# Down.net
KiCad netlist of a schematic drawn in EAGLE
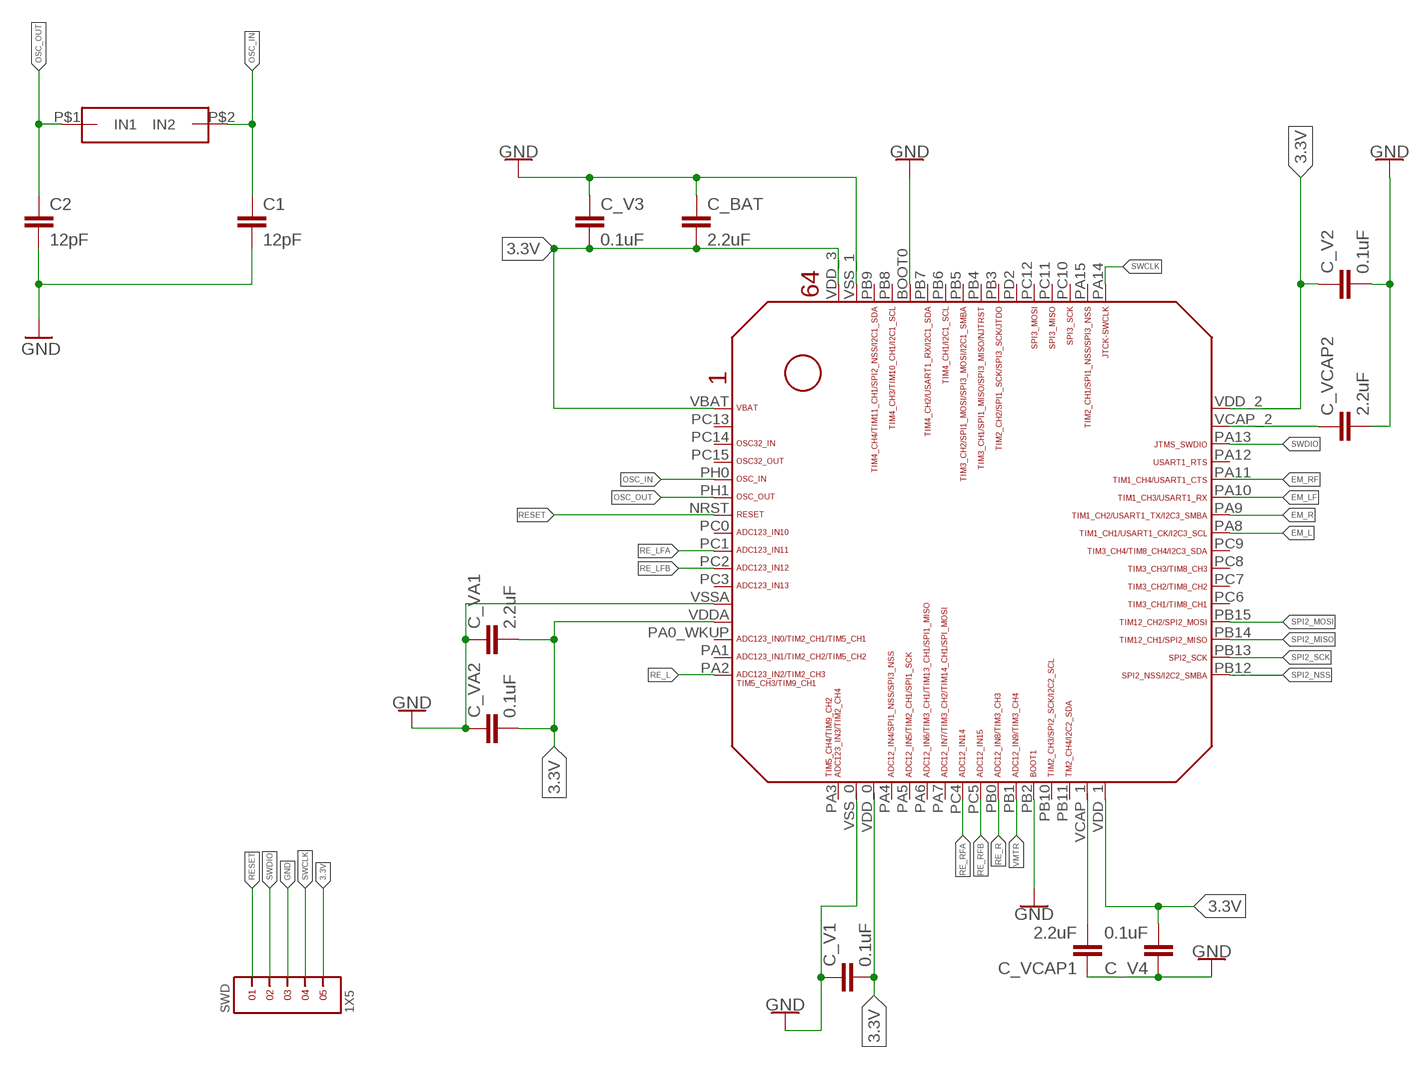
[diagram p0: schematic, sheet 1, part 1 of 3]
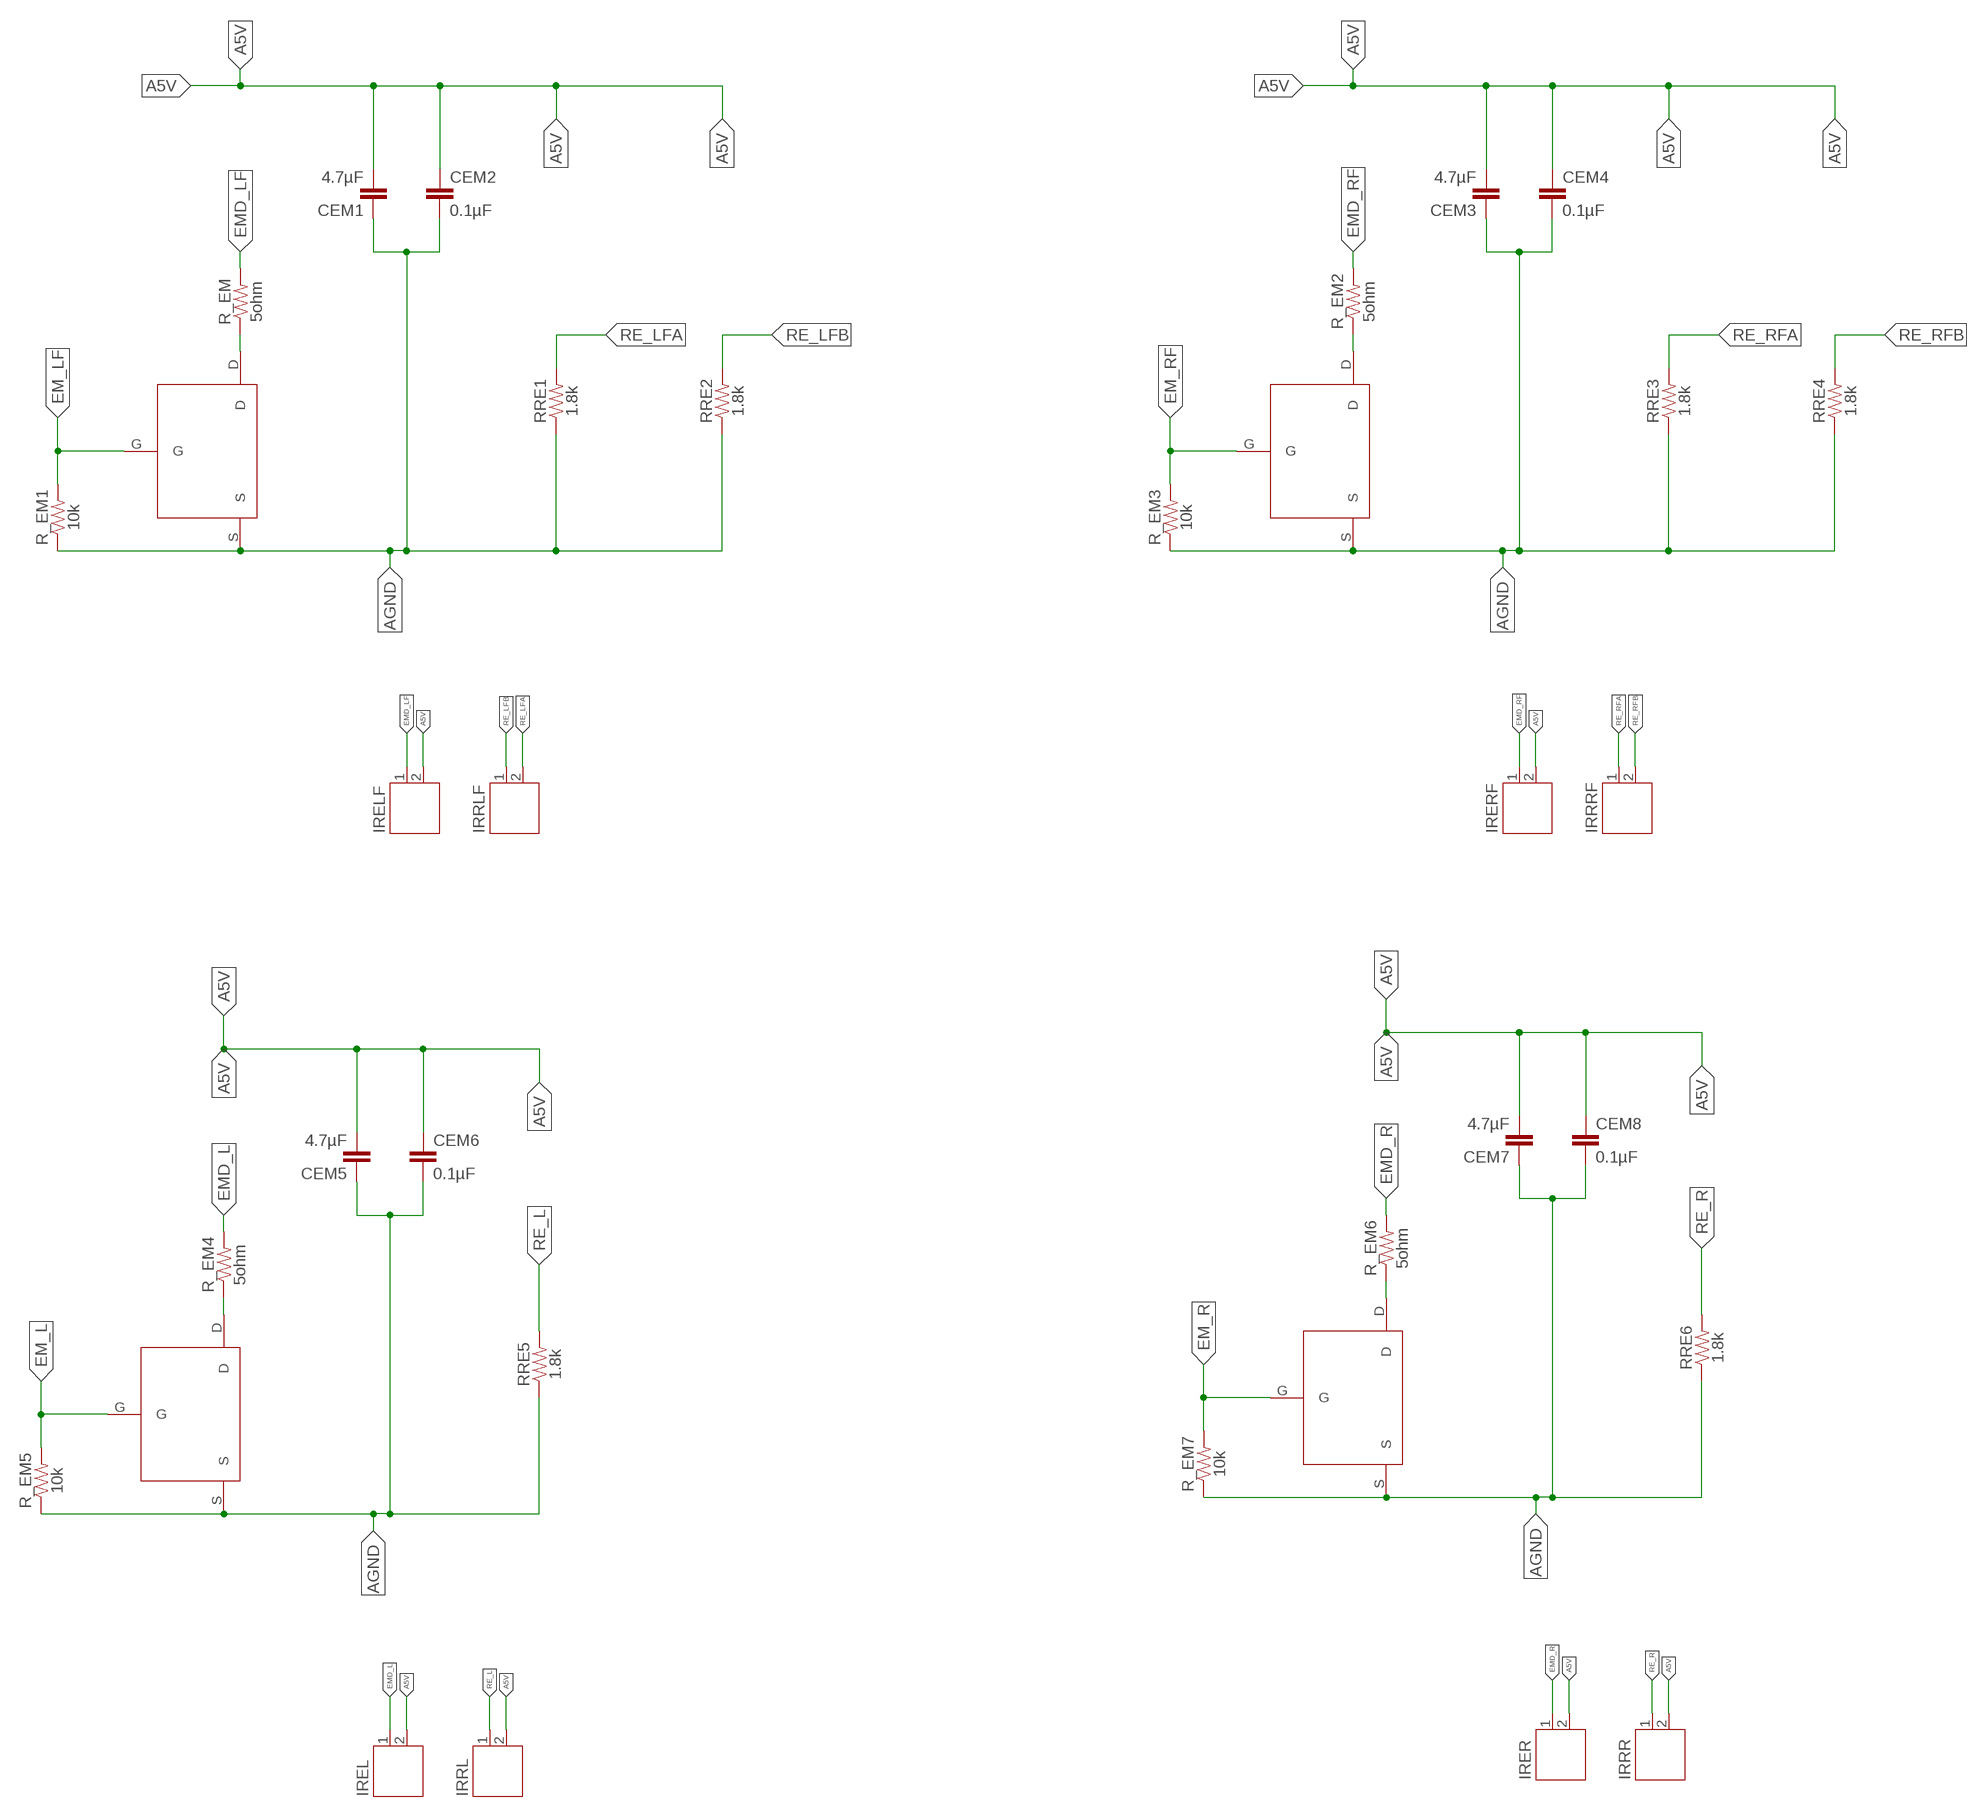
[diagram p1: schematic, sheet 1, part 2 of 3]
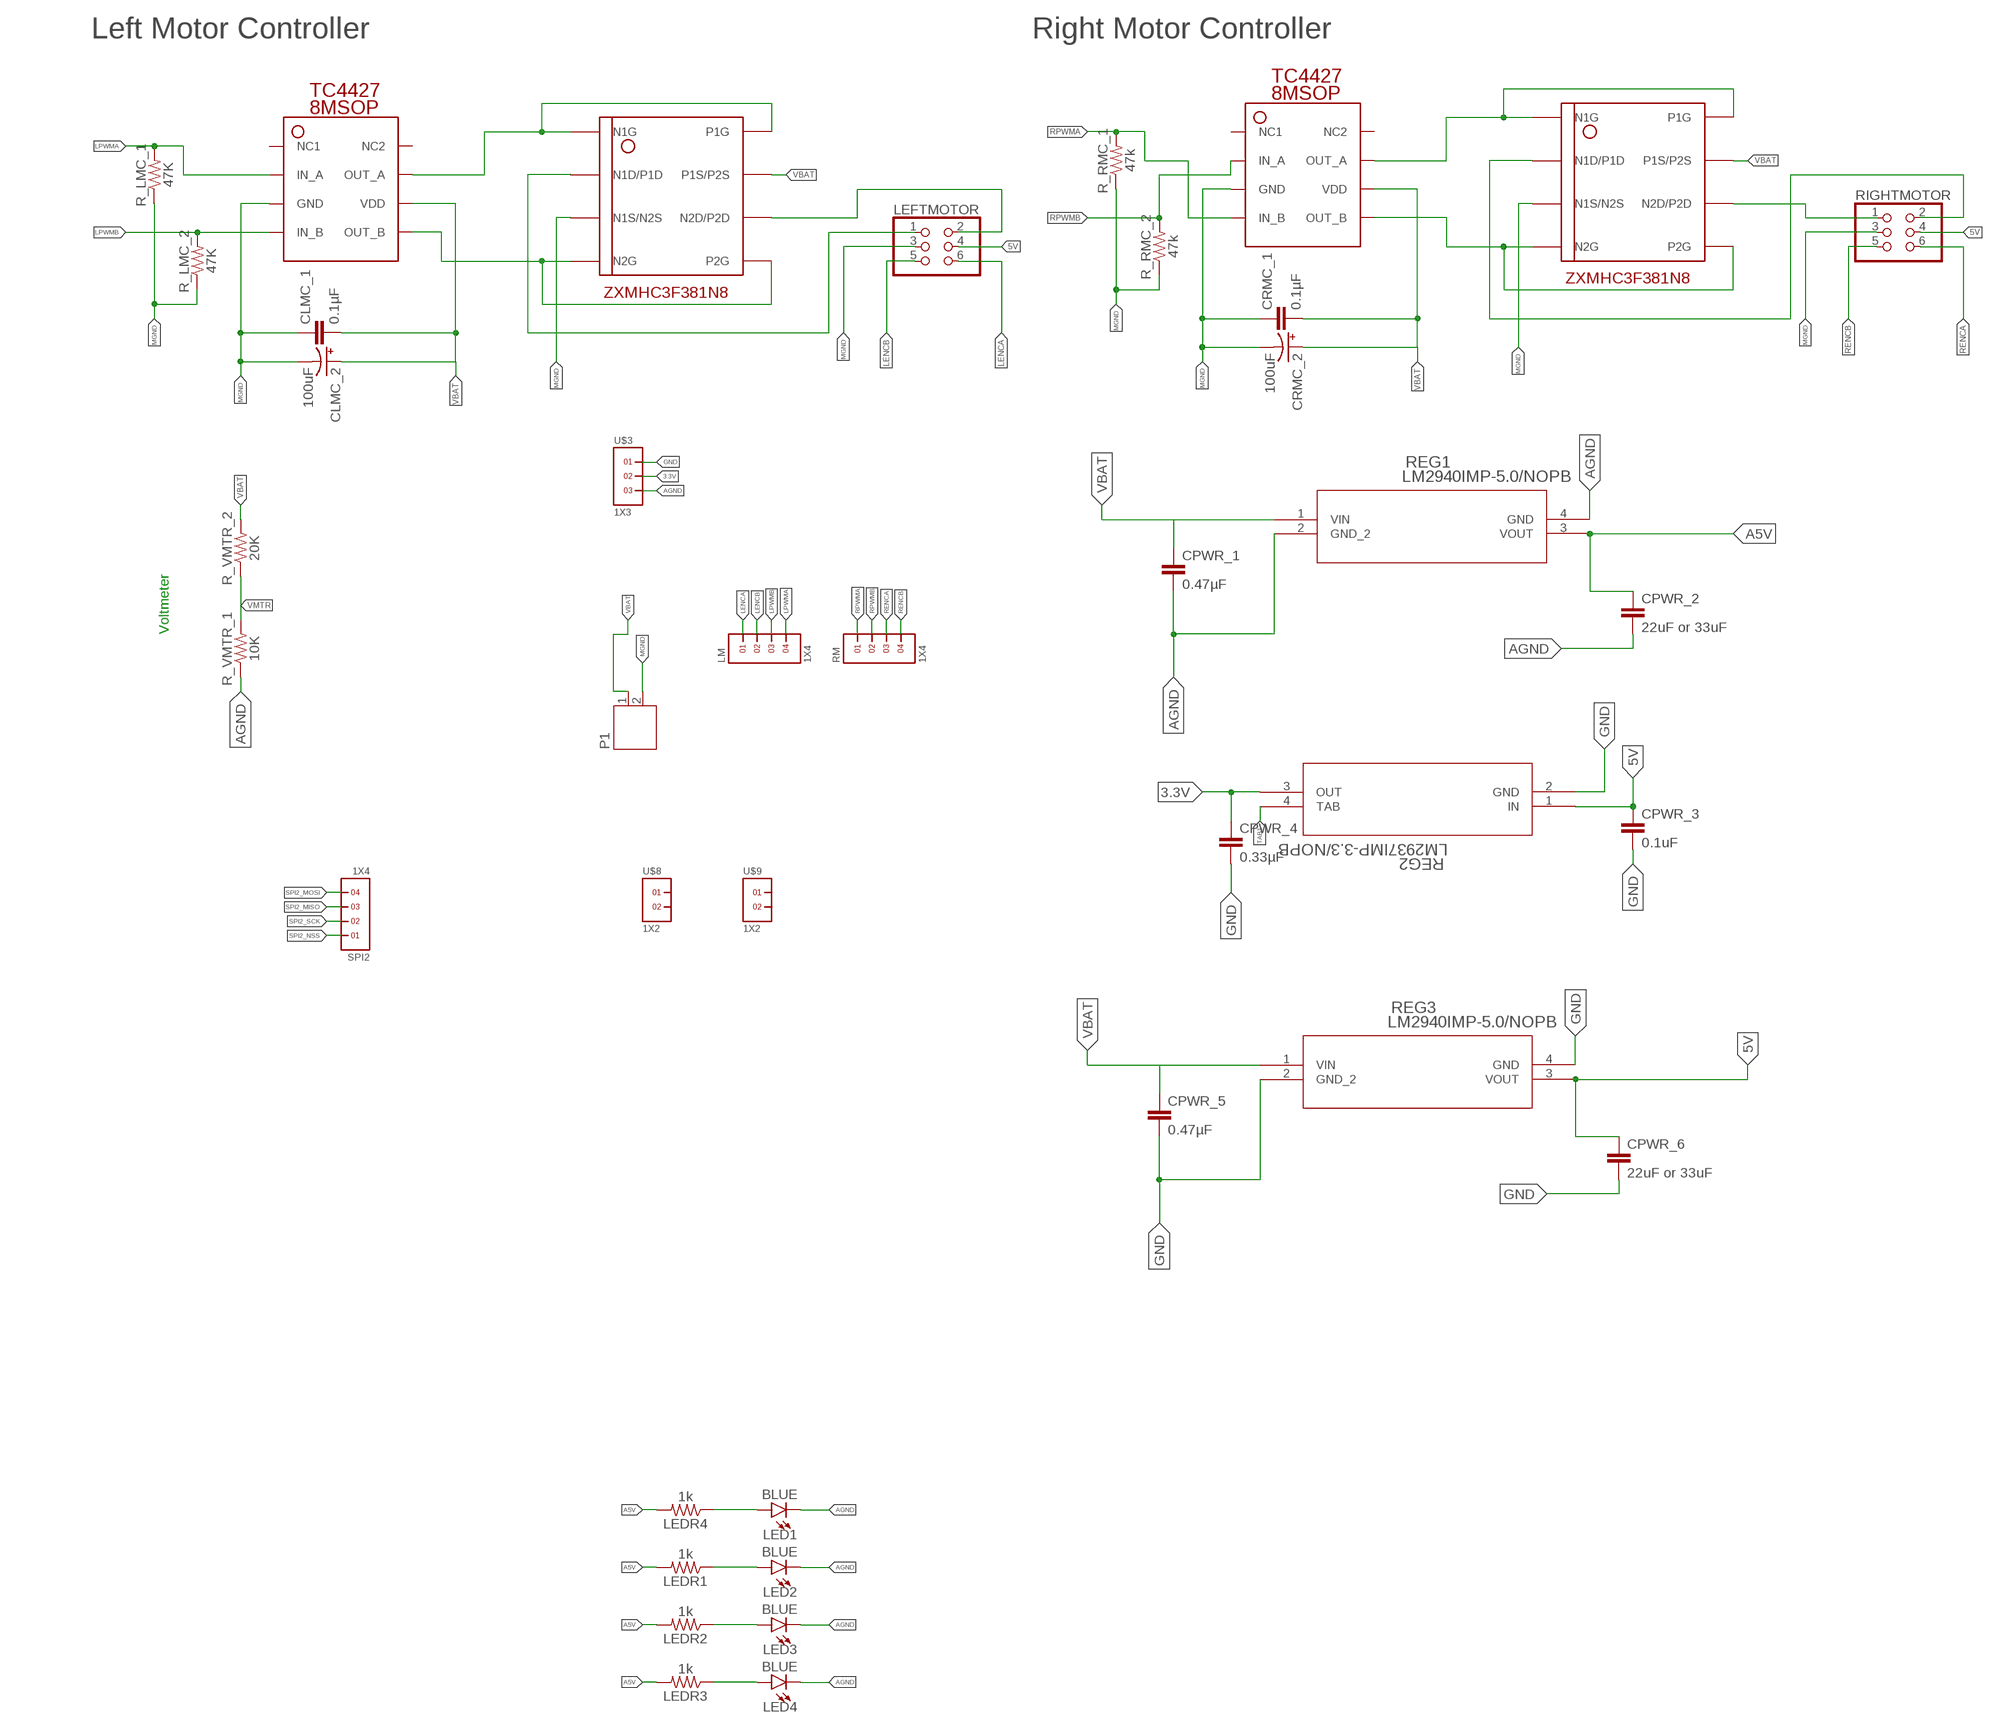
[diagram p2: schematic, sheet 1, part 3 of 3]

(export (version "E")
  (design (tool "Eeschema 10.0.6"))
  (components
    (comp (ref "C1")
      (value "12pF")
      (footprint "eagle-import:0603")
      (libsource (lib "eagle-import") (part "22PF-0603-50V-5%"))
    )
    (comp (ref "C2")
      (value "12pF")
      (footprint "eagle-import:0603")
      (libsource (lib "eagle-import") (part "22PF-0603-50V-5%"))
    )
    (comp (ref "CEM1")
      (value "4.7µF")
      (footprint "eagle-import:0805")
      (libsource (lib "eagle-import") (part "0.33UF/330NF-0805-50V-10%"))
    )
    (comp (ref "CEM2")
      (value "0.1µF")
      (footprint "eagle-import:0805")
      (libsource (lib "eagle-import") (part "0.33UF/330NF-0805-50V-10%"))
    )
    (comp (ref "CEM3")
      (value "4.7µF")
      (footprint "eagle-import:0805")
      (libsource (lib "eagle-import") (part "0.33UF/330NF-0805-50V-10%"))
    )
    (comp (ref "CEM4")
      (value "0.1µF")
      (footprint "eagle-import:0805")
      (libsource (lib "eagle-import") (part "0.33UF/330NF-0805-50V-10%"))
    )
    (comp (ref "CEM5")
      (value "4.7µF")
      (footprint "eagle-import:0805")
      (libsource (lib "eagle-import") (part "0.33UF/330NF-0805-50V-10%"))
    )
    (comp (ref "CEM6")
      (value "0.1µF")
      (footprint "eagle-import:0805")
      (libsource (lib "eagle-import") (part "0.33UF/330NF-0805-50V-10%"))
    )
    (comp (ref "CEM7")
      (value "4.7µF")
      (footprint "eagle-import:0805")
      (libsource (lib "eagle-import") (part "0.33UF/330NF-0805-50V-10%"))
    )
    (comp (ref "CEM8")
      (value "0.1µF")
      (footprint "eagle-import:0805")
      (libsource (lib "eagle-import") (part "0.33UF/330NF-0805-50V-10%"))
    )
    (comp (ref "CLMC_1")
      (value "0.1µF")
      (footprint "eagle-import:0805")
      (libsource (lib "eagle-import") (part "SparkFun-Capacitors_510_0.33UF/330NF-0805-50V-10%"))
    )
    (comp (ref "CLMC_2")
      (value "100uF")
      (footprint "eagle-import:EIA7343")
      (libsource (lib "eagle-import") (part "100UF-POLAR-EIA7343-10V-10%(TANT)"))
    )
    (comp (ref "CPWR_1")
      (value "0.47µF")
      (footprint "eagle-import:0805")
      (libsource (lib "eagle-import") (part "0.33UF/330NF-0805-50V-10%"))
    )
    (comp (ref "CPWR_2")
      (value "22uF or 33uF")
      (footprint "eagle-import:0805")
      (libsource (lib "eagle-import") (part "0.33UF/330NF-0805-50V-10%"))
    )
    (comp (ref "CPWR_3")
      (value "0.1uF")
      (footprint "eagle-import:0805")
      (libsource (lib "eagle-import") (part "0.33UF/330NF-0805-50V-10%"))
    )
    (comp (ref "CPWR_4")
      (value "0.33µF")
      (footprint "eagle-import:0805")
      (libsource (lib "eagle-import") (part "0.33UF/330NF-0805-50V-10%"))
    )
    (comp (ref "CPWR_5")
      (value "0.47µF")
      (footprint "eagle-import:0805")
      (libsource (lib "eagle-import") (part "0.33UF/330NF-0805-50V-10%"))
    )
    (comp (ref "CPWR_6")
      (value "22uF or 33uF")
      (footprint "eagle-import:0805")
      (libsource (lib "eagle-import") (part "0.33UF/330NF-0805-50V-10%"))
    )
    (comp (ref "CRMC_1")
      (value "0.1µF")
      (footprint "eagle-import:0805")
      (libsource (lib "eagle-import") (part "SparkFun-Capacitors_510_0.33UF/330NF-0805-50V-10%"))
    )
    (comp (ref "CRMC_2")
      (value "100uF")
      (footprint "eagle-import:EIA7343")
      (libsource (lib "eagle-import") (part "100UF-POLAR-EIA7343-10V-10%(TANT)"))
    )
    (comp (ref "C_BAT")
      (value "2.2uF")
      (footprint "eagle-import:0805")
      (libsource (lib "eagle-import") (part "22UF-0805-6.3V-20%"))
    )
    (comp (ref "C_V1")
      (value "0.1uF")
      (footprint "eagle-import:0805")
      (libsource (lib "eagle-import") (part "22UF-0805-6.3V-20%"))
    )
    (comp (ref "C_V2")
      (value "0.1uF")
      (footprint "eagle-import:0805")
      (libsource (lib "eagle-import") (part "22UF-0805-6.3V-20%"))
    )
    (comp (ref "C_V3")
      (value "0.1uF")
      (footprint "eagle-import:0805")
      (libsource (lib "eagle-import") (part "22UF-0805-6.3V-20%"))
    )
    (comp (ref "C_V4")
      (value "0.1uF")
      (footprint "eagle-import:0805")
      (libsource (lib "eagle-import") (part "22UF-0805-6.3V-20%"))
    )
    (comp (ref "C_VA1")
      (value "2.2uF")
      (footprint "eagle-import:0805")
      (libsource (lib "eagle-import") (part "22UF-0805-6.3V-20%"))
    )
    (comp (ref "C_VA2")
      (value "0.1uF")
      (footprint "eagle-import:0805")
      (libsource (lib "eagle-import") (part "22UF-0805-6.3V-20%"))
    )
    (comp (ref "C_VCAP1")
      (value "2.2uF")
      (footprint "eagle-import:0805")
      (libsource (lib "eagle-import") (part "22UF-0805-6.3V-20%"))
    )
    (comp (ref "C_VCAP2")
      (value "2.2uF")
      (footprint "eagle-import:0805")
      (libsource (lib "eagle-import") (part "22UF-0805-6.3V-20%"))
    )
    (comp (ref "IREL")
      (value "JST-PH2")
      (footprint "eagle-import:JST-PH2")
      (libsource (lib "eagle-import") (part "JST-PH2"))
    )
    (comp (ref "IRELF")
      (value "JST-PH2")
      (footprint "eagle-import:JST-PH2")
      (libsource (lib "eagle-import") (part "JST-PH2"))
    )
    (comp (ref "IRER")
      (value "JST-PH2")
      (footprint "eagle-import:JST-PH2")
      (libsource (lib "eagle-import") (part "JST-PH2"))
    )
    (comp (ref "IRERF")
      (value "JST-PH2")
      (footprint "eagle-import:JST-PH2")
      (libsource (lib "eagle-import") (part "JST-PH2"))
    )
    (comp (ref "IRRL")
      (value "JST-PH2")
      (footprint "eagle-import:JST-PH2")
      (libsource (lib "eagle-import") (part "JST-PH2"))
    )
    (comp (ref "IRRLF")
      (value "JST-PH2")
      (footprint "eagle-import:JST-PH2")
      (libsource (lib "eagle-import") (part "JST-PH2"))
    )
    (comp (ref "IRRR")
      (value "JST-PH2")
      (footprint "eagle-import:JST-PH2")
      (libsource (lib "eagle-import") (part "JST-PH2"))
    )
    (comp (ref "IRRRF")
      (value "JST-PH2")
      (footprint "eagle-import:JST-PH2")
      (libsource (lib "eagle-import") (part "JST-PH2"))
    )
    (comp (ref "LED1")
      (value "BLUE")
      (footprint "eagle-import:LED-1206")
      (libsource (lib "eagle-import") (part "LED-BLUE1206"))
    )
    (comp (ref "LED2")
      (value "BLUE")
      (footprint "eagle-import:LED-1206")
      (libsource (lib "eagle-import") (part "LED-BLUE1206"))
    )
    (comp (ref "LED3")
      (value "BLUE")
      (footprint "eagle-import:LED-1206")
      (libsource (lib "eagle-import") (part "LED-BLUE1206"))
    )
    (comp (ref "LED4")
      (value "BLUE")
      (footprint "eagle-import:LED-1206")
      (libsource (lib "eagle-import") (part "LED-BLUE1206"))
    )
    (comp (ref "LEDR1")
      (value "1k")
      (footprint "eagle-import:0805")
      (libsource (lib "eagle-import") (part "0.75OHM-0805-1/4W-1%"))
    )
    (comp (ref "LEDR2")
      (value "1k")
      (footprint "eagle-import:0805")
      (libsource (lib "eagle-import") (part "0.75OHM-0805-1/4W-1%"))
    )
    (comp (ref "LEDR3")
      (value "1k")
      (footprint "eagle-import:0805")
      (libsource (lib "eagle-import") (part "0.75OHM-0805-1/4W-1%"))
    )
    (comp (ref "LEDR4")
      (value "1k")
      (footprint "eagle-import:0805")
      (libsource (lib "eagle-import") (part "0.75OHM-0805-1/4W-1%"))
    )
    (comp (ref "LEFTMOTOR")
      (value "PINHD-2X3")
      (footprint "eagle-import:2X03")
      (libsource (lib "eagle-import") (part "PINHD-2X3"))
    )
    (comp (ref "LM")
      (value "1X4")
      (footprint "eagle-import:1X4")
      (libsource (lib "eagle-import") (part "1X4"))
    )
    (comp (ref "P1")
      (value "JST-PH2")
      (footprint "eagle-import:JST-PH2")
      (libsource (lib "eagle-import") (part "JST-PH2"))
    )
    (comp (ref "REG1")
      (value "LM2940IMP-5.0/NOPB")
      (footprint "eagle-import:MP04A")
      (fields
        (field (name "MANUFACTURER_PART_NUMBER") "LM2940IMP5.0NOPB")
        (field (name "COPYRIGHT") "Copyright C 2015 Accelerated Designs. All rights reserved")
      )
      (libsource (lib "eagle-import") (part "LM2940IMP-5.0/NOPB"))
    )
    (comp (ref "REG2")
      (value "LM2937IMP-3.3/NOPB")
      (footprint "eagle-import:MP04A")
      (fields
        (field (name "MANUFACTURER_PART_NUMBER") "lm2937imp3_3nopb")
        (field (name "COPYRIGHT") "Copyright C 2015 Accelerated Designs. All rights reserved")
      )
      (libsource (lib "eagle-import") (part "LM2937IMP-3.3/NOPB"))
    )
    (comp (ref "REG3")
      (value "LM2940IMP-5.0/NOPB")
      (footprint "eagle-import:MP04A")
      (fields
        (field (name "MANUFACTURER_PART_NUMBER") "LM2940IMP5.0NOPB")
        (field (name "COPYRIGHT") "Copyright C 2015 Accelerated Designs. All rights reserved")
      )
      (libsource (lib "eagle-import") (part "LM2940IMP-5.0/NOPB"))
    )
    (comp (ref "RIGHTMOTOR")
      (value "PINHD-2X3")
      (footprint "eagle-import:2X03")
      (libsource (lib "eagle-import") (part "PINHD-2X3"))
    )
    (comp (ref "RM")
      (value "1X4")
      (footprint "eagle-import:1X4")
      (libsource (lib "eagle-import") (part "1X4"))
    )
    (comp (ref "RRE1")
      (value "1.8k")
      (footprint "eagle-import:0805")
      (libsource (lib "eagle-import") (part "0.75OHM-0805-1/4W-1%"))
    )
    (comp (ref "RRE2")
      (value "1.8k")
      (footprint "eagle-import:0805")
      (libsource (lib "eagle-import") (part "0.75OHM-0805-1/4W-1%"))
    )
    (comp (ref "RRE3")
      (value "1.8k")
      (footprint "eagle-import:0805")
      (libsource (lib "eagle-import") (part "0.75OHM-0805-1/4W-1%"))
    )
    (comp (ref "RRE4")
      (value "1.8k")
      (footprint "eagle-import:0805")
      (libsource (lib "eagle-import") (part "0.75OHM-0805-1/4W-1%"))
    )
    (comp (ref "RRE5")
      (value "1.8k")
      (footprint "eagle-import:0805")
      (libsource (lib "eagle-import") (part "0.75OHM-0805-1/4W-1%"))
    )
    (comp (ref "RRE6")
      (value "1.8k")
      (footprint "eagle-import:0805")
      (libsource (lib "eagle-import") (part "0.75OHM-0805-1/4W-1%"))
    )
    (comp (ref "R_EM")
      (value "5ohm")
      (footprint "eagle-import:0805")
      (libsource (lib "eagle-import") (part "0.75OHM-0805-1/4W-1%"))
    )
    (comp (ref "R_EM1")
      (value "10k")
      (footprint "eagle-import:0805")
      (libsource (lib "eagle-import") (part "0.75OHM-0805-1/4W-1%"))
    )
    (comp (ref "R_EM2")
      (value "5ohm")
      (footprint "eagle-import:0805")
      (libsource (lib "eagle-import") (part "0.75OHM-0805-1/4W-1%"))
    )
    (comp (ref "R_EM3")
      (value "10k")
      (footprint "eagle-import:0805")
      (libsource (lib "eagle-import") (part "0.75OHM-0805-1/4W-1%"))
    )
    (comp (ref "R_EM4")
      (value "5ohm")
      (footprint "eagle-import:0805")
      (libsource (lib "eagle-import") (part "0.75OHM-0805-1/4W-1%"))
    )
    (comp (ref "R_EM5")
      (value "10k")
      (footprint "eagle-import:0805")
      (libsource (lib "eagle-import") (part "0.75OHM-0805-1/4W-1%"))
    )
    (comp (ref "R_EM6")
      (value "5ohm")
      (footprint "eagle-import:0805")
      (libsource (lib "eagle-import") (part "0.75OHM-0805-1/4W-1%"))
    )
    (comp (ref "R_EM7")
      (value "10k")
      (footprint "eagle-import:0805")
      (libsource (lib "eagle-import") (part "0.75OHM-0805-1/4W-1%"))
    )
    (comp (ref "R_LMC_1")
      (value "47K")
      (footprint "eagle-import:0805")
      (libsource (lib "eagle-import") (part "SparkFun-Resistors_532_0.75OHM-0805-1/4W-1%"))
    )
    (comp (ref "R_LMC_2")
      (value "47K")
      (footprint "eagle-import:0805")
      (libsource (lib "eagle-import") (part "SparkFun-Resistors_532_0.75OHM-0805-1/4W-1%"))
    )
    (comp (ref "R_RMC_1")
      (value "47k")
      (footprint "eagle-import:0805")
      (libsource (lib "eagle-import") (part "SparkFun-Resistors_532_0.75OHM-0805-1/4W-1%"))
    )
    (comp (ref "R_RMC_2")
      (value "47k")
      (footprint "eagle-import:0805")
      (libsource (lib "eagle-import") (part "SparkFun-Resistors_532_0.75OHM-0805-1/4W-1%"))
    )
    (comp (ref "R_VMTR_1")
      (value "10K")
      (footprint "eagle-import:0805")
      (libsource (lib "eagle-import") (part "0.75OHM-0805-1/4W-1%"))
    )
    (comp (ref "R_VMTR_2")
      (value "20K")
      (footprint "eagle-import:0805")
      (libsource (lib "eagle-import") (part "0.75OHM-0805-1/4W-1%"))
    )
    (comp (ref "SPI2")
      (value "1X4")
      (footprint "eagle-import:1X4")
      (libsource (lib "eagle-import") (part "1X4"))
    )
    (comp (ref "SWD")
      (value "1X5")
      (footprint "eagle-import:1X5")
      (libsource (lib "eagle-import") (part "1X5"))
    )
    (comp (ref "U$1")
      (value "STM32F405/415_LQFP64")
      (footprint "eagle-import:STM32F405_415_LQFP64")
      (libsource (lib "eagle-import") (part "STM32F405/415_LQFP64"))
    )
    (comp (ref "U$2")
      (value "OSC")
      (footprint "eagle-import:OSC")
      (libsource (lib "eagle-import") (part "OSC"))
    )
    (comp (ref "U$3")
      (value "1X3")
      (footprint "eagle-import:1X3")
      (libsource (lib "eagle-import") (part "1X3"))
    )
    (comp (ref "U$4")
      (value "MCH3474")
      (footprint "eagle-import:MCH3474")
      (libsource (lib "eagle-import") (part "MCH3474"))
    )
    (comp (ref "U$5")
      (value "MCH3474")
      (footprint "eagle-import:MCH3474")
      (libsource (lib "eagle-import") (part "MCH3474"))
    )
    (comp (ref "U$6")
      (value "MCH3474")
      (footprint "eagle-import:MCH3474")
      (libsource (lib "eagle-import") (part "MCH3474"))
    )
    (comp (ref "U$7")
      (value "MCH3474")
      (footprint "eagle-import:MCH3474")
      (libsource (lib "eagle-import") (part "MCH3474"))
    )
    (comp (ref "U$8")
      (value "1X2")
      (footprint "eagle-import:1X2")
      (libsource (lib "eagle-import") (part "1X2"))
    )
    (comp (ref "U$9")
      (value "1X2")
      (footprint "eagle-import:1X2")
      (libsource (lib "eagle-import") (part "1X2"))
    )
    (comp (ref "U$15")
      (value "TC4427(8MSOP)")
      (footprint "eagle-import:TC4427(8MSOP)")
      (libsource (lib "eagle-import") (part "TC4427(8MSOP)"))
    )
    (comp (ref "U$16")
      (value "ZXMHC3F381N8")
      (footprint "eagle-import:ZXMHC3F381N8")
      (libsource (lib "eagle-import") (part "ZXMHC3F381N8"))
    )
    (comp (ref "U$17")
      (value "TC4427(8MSOP)")
      (footprint "eagle-import:TC4427(8MSOP)")
      (libsource (lib "eagle-import") (part "TC4427(8MSOP)"))
    )
    (comp (ref "U$18")
      (value "ZXMHC3F381N8")
      (footprint "eagle-import:ZXMHC3F381N8")
      (libsource (lib "eagle-import") (part "ZXMHC3F381N8"))
    )
  )
  (nets
    (net (code "1") (name "3.3V") (class "Default")
      (node (ref "CPWR_4") (pin "1") (pinfunction "1_1") (pintype "passive"))
      (node (ref "C_BAT") (pin "2") (pinfunction "2_2") (pintype "passive"))
      (node (ref "C_V1") (pin "2") (pinfunction "2_2") (pintype "passive"))
      (node (ref "C_V2") (pin "1") (pinfunction "1_1") (pintype "passive"))
      (node (ref "C_V3") (pin "2") (pinfunction "2_2") (pintype "passive"))
      (node (ref "C_V4") (pin "2") (pinfunction "2_2") (pintype "passive"))
      (node (ref "C_VA1") (pin "2") (pinfunction "2_2") (pintype "passive"))
      (node (ref "C_VA2") (pin "2") (pinfunction "2_2") (pintype "passive"))
      (node (ref "REG2") (pin "3") (pinfunction "OUT_3") (pintype "power_in"))
      (node (ref "SWD") (pin "5") (pinfunction "5_5") (pintype "bidirectional"))
      (node (ref "U$1") (pin "VBAT") (pinfunction "VBAT_VBAT") (pintype "bidirectional"))
      (node (ref "U$1") (pin "VDDA") (pinfunction "VDDA_VDDA") (pintype "bidirectional"))
      (node (ref "U$1") (pin "VDD_0") (pinfunction "VDD_0_VDD_0") (pintype "bidirectional"))
      (node (ref "U$1") (pin "VDD_1") (pinfunction "VDD_1_VDD_1") (pintype "bidirectional"))
      (node (ref "U$1") (pin "VDD_2") (pinfunction "VDD_2_VDD_2") (pintype "bidirectional"))
      (node (ref "U$1") (pin "VDD_3") (pinfunction "VDD_3_VDD_3") (pintype "bidirectional"))
      (node (ref "U$3") (pin "2") (pinfunction "2_2") (pintype "bidirectional"))
    )
    (net (code "2") (name "5V") (class "Default")
      (node (ref "CPWR_3") (pin "1") (pinfunction "1_1") (pintype "passive"))
      (node (ref "CPWR_6") (pin "1") (pinfunction "1_1") (pintype "passive"))
      (node (ref "LEFTMOTOR") (pin "4") (pinfunction "4_4") (pintype "passive"))
      (node (ref "REG2") (pin "1") (pinfunction "IN_1") (pintype "power_in"))
      (node (ref "REG3") (pin "3") (pinfunction "VOUT_3") (pintype "output"))
      (node (ref "RIGHTMOTOR") (pin "4") (pinfunction "4_4") (pintype "passive"))
    )
    (net (code "3") (name "A5V") (class "Default")
      (node (ref "CEM1") (pin "2") (pinfunction "2_2") (pintype "passive"))
      (node (ref "CEM2") (pin "1") (pinfunction "1_1") (pintype "passive"))
      (node (ref "CEM3") (pin "2") (pinfunction "2_2") (pintype "passive"))
      (node (ref "CEM4") (pin "1") (pinfunction "1_1") (pintype "passive"))
      (node (ref "CEM5") (pin "2") (pinfunction "2_2") (pintype "passive"))
      (node (ref "CEM6") (pin "1") (pinfunction "1_1") (pintype "passive"))
      (node (ref "CEM7") (pin "2") (pinfunction "2_2") (pintype "passive"))
      (node (ref "CEM8") (pin "1") (pinfunction "1_1") (pintype "passive"))
      (node (ref "CPWR_2") (pin "1") (pinfunction "1_1") (pintype "passive"))
      (node (ref "IREL") (pin "2") (pinfunction "2_2") (pintype "passive"))
      (node (ref "IRELF") (pin "2") (pinfunction "2_2") (pintype "passive"))
      (node (ref "IRER") (pin "2") (pinfunction "2_2") (pintype "passive"))
      (node (ref "IRERF") (pin "2") (pinfunction "2_2") (pintype "passive"))
      (node (ref "IRRL") (pin "2") (pinfunction "2_2") (pintype "passive"))
      (node (ref "IRRR") (pin "2") (pinfunction "2_2") (pintype "passive"))
      (node (ref "LEDR1") (pin "2") (pinfunction "2_2") (pintype "passive"))
      (node (ref "LEDR2") (pin "2") (pinfunction "2_2") (pintype "passive"))
      (node (ref "LEDR3") (pin "2") (pinfunction "2_2") (pintype "passive"))
      (node (ref "LEDR4") (pin "2") (pinfunction "2_2") (pintype "passive"))
      (node (ref "REG1") (pin "3") (pinfunction "VOUT_3") (pintype "output"))
    )
    (net (code "4") (name "AGND") (class "Default")
      (node (ref "CEM1") (pin "1") (pinfunction "1_1") (pintype "passive"))
      (node (ref "CEM2") (pin "2") (pinfunction "2_2") (pintype "passive"))
      (node (ref "CEM3") (pin "1") (pinfunction "1_1") (pintype "passive"))
      (node (ref "CEM4") (pin "2") (pinfunction "2_2") (pintype "passive"))
      (node (ref "CEM5") (pin "1") (pinfunction "1_1") (pintype "passive"))
      (node (ref "CEM6") (pin "2") (pinfunction "2_2") (pintype "passive"))
      (node (ref "CEM7") (pin "1") (pinfunction "1_1") (pintype "passive"))
      (node (ref "CEM8") (pin "2") (pinfunction "2_2") (pintype "passive"))
      (node (ref "CPWR_1") (pin "2") (pinfunction "2_2") (pintype "passive"))
      (node (ref "CPWR_2") (pin "2") (pinfunction "2_2") (pintype "passive"))
      (node (ref "LED1") (pin "C") (pinfunction "C_C") (pintype "passive"))
      (node (ref "LED2") (pin "C") (pinfunction "C_C") (pintype "passive"))
      (node (ref "LED3") (pin "C") (pinfunction "C_C") (pintype "passive"))
      (node (ref "LED4") (pin "C") (pinfunction "C_C") (pintype "passive"))
      (node (ref "REG1") (pin "2") (pinfunction "GND_2_2") (pintype "power_in"))
      (node (ref "REG1") (pin "4") (pinfunction "GND_4") (pintype "power_in"))
      (node (ref "RRE1") (pin "1") (pinfunction "1_1") (pintype "passive"))
      (node (ref "RRE2") (pin "1") (pinfunction "1_1") (pintype "passive"))
      (node (ref "RRE3") (pin "1") (pinfunction "1_1") (pintype "passive"))
      (node (ref "RRE4") (pin "1") (pinfunction "1_1") (pintype "passive"))
      (node (ref "RRE5") (pin "1") (pinfunction "1_1") (pintype "passive"))
      (node (ref "RRE6") (pin "1") (pinfunction "1_1") (pintype "passive"))
      (node (ref "R_EM1") (pin "1") (pinfunction "1_1") (pintype "passive"))
      (node (ref "R_EM3") (pin "1") (pinfunction "1_1") (pintype "passive"))
      (node (ref "R_EM5") (pin "1") (pinfunction "1_1") (pintype "passive"))
      (node (ref "R_EM7") (pin "1") (pinfunction "1_1") (pintype "passive"))
      (node (ref "R_VMTR_1") (pin "1") (pinfunction "1_1") (pintype "passive"))
      (node (ref "U$3") (pin "3") (pinfunction "3_3") (pintype "bidirectional"))
      (node (ref "U$4") (pin "S") (pinfunction "S_S") (pintype "bidirectional"))
      (node (ref "U$5") (pin "S") (pinfunction "S_S") (pintype "bidirectional"))
      (node (ref "U$6") (pin "S") (pinfunction "S_S") (pintype "bidirectional"))
      (node (ref "U$7") (pin "S") (pinfunction "S_S") (pintype "bidirectional"))
    )
    (net (code "5") (name "EMD_L") (class "Default")
      (node (ref "IREL") (pin "1") (pinfunction "1_1") (pintype "passive"))
      (node (ref "R_EM4") (pin "2") (pinfunction "2_2") (pintype "passive"))
    )
    (net (code "6") (name "EMD_LF") (class "Default")
      (node (ref "IRELF") (pin "1") (pinfunction "1_1") (pintype "passive"))
      (node (ref "R_EM") (pin "2") (pinfunction "2_2") (pintype "passive"))
    )
    (net (code "7") (name "EMD_R") (class "Default")
      (node (ref "IRER") (pin "1") (pinfunction "1_1") (pintype "passive"))
      (node (ref "R_EM6") (pin "2") (pinfunction "2_2") (pintype "passive"))
    )
    (net (code "8") (name "EMD_RF") (class "Default")
      (node (ref "IRERF") (pin "1") (pinfunction "1_1") (pintype "passive"))
      (node (ref "R_EM2") (pin "2") (pinfunction "2_2") (pintype "passive"))
    )
    (net (code "9") (name "EM_L") (class "Default")
      (node (ref "R_EM5") (pin "2") (pinfunction "2_2") (pintype "passive"))
      (node (ref "U$1") (pin "PA8") (pinfunction "PA8_PA8") (pintype "bidirectional"))
      (node (ref "U$4") (pin "G") (pinfunction "G_G") (pintype "bidirectional"))
    )
    (net (code "10") (name "EM_LF") (class "Default")
      (node (ref "R_EM1") (pin "2") (pinfunction "2_2") (pintype "passive"))
      (node (ref "U$1") (pin "PA10") (pinfunction "PA10_PA10") (pintype "bidirectional"))
      (node (ref "U$5") (pin "G") (pinfunction "G_G") (pintype "bidirectional"))
    )
    (net (code "11") (name "EM_R") (class "Default")
      (node (ref "R_EM7") (pin "2") (pinfunction "2_2") (pintype "passive"))
      (node (ref "U$1") (pin "PA9") (pinfunction "PA9_PA9") (pintype "bidirectional"))
      (node (ref "U$7") (pin "G") (pinfunction "G_G") (pintype "bidirectional"))
    )
    (net (code "12") (name "EM_RF") (class "Default")
      (node (ref "R_EM3") (pin "2") (pinfunction "2_2") (pintype "passive"))
      (node (ref "U$1") (pin "PA11") (pinfunction "PA11_PA11") (pintype "bidirectional"))
      (node (ref "U$6") (pin "G") (pinfunction "G_G") (pintype "bidirectional"))
    )
    (net (code "13") (name "GND") (class "Default")
      (node (ref "C1") (pin "2") (pinfunction "2_2") (pintype "passive"))
      (node (ref "C2") (pin "2") (pinfunction "2_2") (pintype "passive"))
      (node (ref "CPWR_3") (pin "2") (pinfunction "2_2") (pintype "passive"))
      (node (ref "CPWR_4") (pin "2") (pinfunction "2_2") (pintype "passive"))
      (node (ref "CPWR_5") (pin "2") (pinfunction "2_2") (pintype "passive"))
      (node (ref "CPWR_6") (pin "2") (pinfunction "2_2") (pintype "passive"))
      (node (ref "C_BAT") (pin "1") (pinfunction "1_1") (pintype "passive"))
      (node (ref "C_V1") (pin "1") (pinfunction "1_1") (pintype "passive"))
      (node (ref "C_V2") (pin "2") (pinfunction "2_2") (pintype "passive"))
      (node (ref "C_V3") (pin "1") (pinfunction "1_1") (pintype "passive"))
      (node (ref "C_V4") (pin "1") (pinfunction "1_1") (pintype "passive"))
      (node (ref "C_VA1") (pin "1") (pinfunction "1_1") (pintype "passive"))
      (node (ref "C_VA2") (pin "1") (pinfunction "1_1") (pintype "passive"))
      (node (ref "C_VCAP1") (pin "1") (pinfunction "1_1") (pintype "passive"))
      (node (ref "C_VCAP2") (pin "2") (pinfunction "2_2") (pintype "passive"))
      (node (ref "REG2") (pin "2") (pinfunction "GND_2") (pintype "power_in"))
      (node (ref "REG3") (pin "2") (pinfunction "GND_2_2") (pintype "power_in"))
      (node (ref "REG3") (pin "4") (pinfunction "GND_4") (pintype "power_in"))
      (node (ref "SWD") (pin "3") (pinfunction "3_3") (pintype "bidirectional"))
      (node (ref "U$1") (pin "BOOT0") (pinfunction "BOOT0_BOOT0") (pintype "bidirectional"))
      (node (ref "U$1") (pin "PB2") (pinfunction "PB2_PB2") (pintype "bidirectional"))
      (node (ref "U$1") (pin "VSSA") (pinfunction "VSSA_VSSA") (pintype "bidirectional"))
      (node (ref "U$1") (pin "VSS_0") (pinfunction "VSS_0_VSS_0") (pintype "bidirectional"))
      (node (ref "U$1") (pin "VSS_1") (pinfunction "VSS_1_VSS_1") (pintype "bidirectional"))
      (node (ref "U$3") (pin "1") (pinfunction "1_1") (pintype "bidirectional"))
    )
    (net (code "14") (name "LENCA") (class "Default")
      (node (ref "LEFTMOTOR") (pin "6") (pinfunction "6_6") (pintype "passive"))
      (node (ref "LM") (pin "1") (pinfunction "1_1") (pintype "bidirectional"))
    )
    (net (code "15") (name "LENCB") (class "Default")
      (node (ref "LEFTMOTOR") (pin "5") (pinfunction "5_5") (pintype "passive"))
      (node (ref "LM") (pin "2") (pinfunction "2_2") (pintype "bidirectional"))
    )
    (net (code "16") (name "LPWMA") (class "Default")
      (node (ref "LM") (pin "4") (pinfunction "4_4") (pintype "bidirectional"))
      (node (ref "R_LMC_1") (pin "2") (pinfunction "2_2") (pintype "passive"))
      (node (ref "U$15") (pin "IN_A") (pinfunction "IN_A_IN_A") (pintype "bidirectional"))
    )
    (net (code "17") (name "LPWMB") (class "Default")
      (node (ref "LM") (pin "3") (pinfunction "3_3") (pintype "bidirectional"))
      (node (ref "R_LMC_2") (pin "2") (pinfunction "2_2") (pintype "passive"))
      (node (ref "U$15") (pin "IN_B") (pinfunction "IN_B_IN_B") (pintype "bidirectional"))
    )
    (net (code "18") (name "MGND") (class "Default")
      (node (ref "CLMC_1") (pin "1") (pinfunction "1_1") (pintype "passive"))
      (node (ref "CLMC_2") (pin "C") (pinfunction "-_C") (pintype "passive"))
      (node (ref "CRMC_1") (pin "1") (pinfunction "1_1") (pintype "passive"))
      (node (ref "CRMC_2") (pin "C") (pinfunction "-_C") (pintype "passive"))
      (node (ref "LEFTMOTOR") (pin "3") (pinfunction "3_3") (pintype "passive"))
      (node (ref "P1") (pin "2") (pinfunction "2_2") (pintype "passive"))
      (node (ref "RIGHTMOTOR") (pin "3") (pinfunction "3_3") (pintype "passive"))
      (node (ref "R_LMC_1") (pin "1") (pinfunction "1_1") (pintype "passive"))
      (node (ref "R_LMC_2") (pin "1") (pinfunction "1_1") (pintype "passive"))
      (node (ref "R_RMC_1") (pin "1") (pinfunction "1_1") (pintype "passive"))
      (node (ref "R_RMC_2") (pin "1") (pinfunction "1_1") (pintype "passive"))
      (node (ref "U$15") (pin "GND") (pinfunction "GND_GND") (pintype "bidirectional"))
      (node (ref "U$16") (pin "N1S/N2S") (pinfunction "N1S/N2S_N1S/N2S") (pintype "bidirectional"))
      (node (ref "U$17") (pin "GND") (pinfunction "GND_GND") (pintype "bidirectional"))
      (node (ref "U$18") (pin "N1S/N2S") (pinfunction "N1S/N2S_N1S/N2S") (pintype "bidirectional"))
    )
    (net (code "19") (name "Net-(C_VCAP1-Pad2)") (class "Default")
      (node (ref "C_VCAP1") (pin "2") (pinfunction "2_2") (pintype "passive"))
      (node (ref "U$1") (pin "VCAP_1") (pinfunction "VCAP_1_VCAP_1") (pintype "bidirectional"))
    )
    (net (code "20") (name "Net-(C_VCAP2-Pad1)") (class "Default")
      (node (ref "C_VCAP2") (pin "1") (pinfunction "1_1") (pintype "passive"))
      (node (ref "U$1") (pin "VCAP_2") (pinfunction "VCAP_2_VCAP_2") (pintype "bidirectional"))
    )
    (net (code "21") (name "Net-(LED1-PadA)") (class "Default")
      (node (ref "LED1") (pin "A") (pinfunction "A_A") (pintype "passive"))
      (node (ref "LEDR4") (pin "1") (pinfunction "1_1") (pintype "passive"))
    )
    (net (code "22") (name "Net-(LED2-PadA)") (class "Default")
      (node (ref "LED2") (pin "A") (pinfunction "A_A") (pintype "passive"))
      (node (ref "LEDR1") (pin "1") (pinfunction "1_1") (pintype "passive"))
    )
    (net (code "23") (name "Net-(LED3-PadA)") (class "Default")
      (node (ref "LED3") (pin "A") (pinfunction "A_A") (pintype "passive"))
      (node (ref "LEDR2") (pin "1") (pinfunction "1_1") (pintype "passive"))
    )
    (net (code "24") (name "Net-(LED4-PadA)") (class "Default")
      (node (ref "LED4") (pin "A") (pinfunction "A_A") (pintype "passive"))
      (node (ref "LEDR3") (pin "1") (pinfunction "1_1") (pintype "passive"))
    )
    (net (code "25") (name "Net-(LEFTMOTOR-Pad1)") (class "Default")
      (node (ref "LEFTMOTOR") (pin "1") (pinfunction "1_1") (pintype "passive"))
      (node (ref "U$16") (pin "N1D/P1D") (pinfunction "N1D/P1D_N1D/P1D") (pintype "bidirectional"))
    )
    (net (code "26") (name "Net-(LEFTMOTOR-Pad2)") (class "Default")
      (node (ref "LEFTMOTOR") (pin "2") (pinfunction "2_2") (pintype "passive"))
      (node (ref "U$16") (pin "N2D/P2D") (pinfunction "N2D/P2D_N2D/P2D") (pintype "bidirectional"))
    )
    (net (code "27") (name "Net-(RIGHTMOTOR-Pad1)") (class "Default")
      (node (ref "RIGHTMOTOR") (pin "1") (pinfunction "1_1") (pintype "passive"))
      (node (ref "U$18") (pin "N2D/P2D") (pinfunction "N2D/P2D_N2D/P2D") (pintype "bidirectional"))
    )
    (net (code "28") (name "Net-(RIGHTMOTOR-Pad2)") (class "Default")
      (node (ref "RIGHTMOTOR") (pin "2") (pinfunction "2_2") (pintype "passive"))
      (node (ref "U$18") (pin "N1D/P1D") (pinfunction "N1D/P1D_N1D/P1D") (pintype "bidirectional"))
    )
    (net (code "29") (name "Net-(R_EM-Pad1)") (class "Default")
      (node (ref "R_EM") (pin "1") (pinfunction "1_1") (pintype "passive"))
      (node (ref "U$5") (pin "D") (pinfunction "D_D") (pintype "bidirectional"))
    )
    (net (code "30") (name "Net-(R_EM2-Pad1)") (class "Default")
      (node (ref "R_EM2") (pin "1") (pinfunction "1_1") (pintype "passive"))
      (node (ref "U$6") (pin "D") (pinfunction "D_D") (pintype "bidirectional"))
    )
    (net (code "31") (name "Net-(R_EM4-Pad1)") (class "Default")
      (node (ref "R_EM4") (pin "1") (pinfunction "1_1") (pintype "passive"))
      (node (ref "U$4") (pin "D") (pinfunction "D_D") (pintype "bidirectional"))
    )
    (net (code "32") (name "Net-(R_EM6-Pad1)") (class "Default")
      (node (ref "R_EM6") (pin "1") (pinfunction "1_1") (pintype "passive"))
      (node (ref "U$7") (pin "D") (pinfunction "D_D") (pintype "bidirectional"))
    )
    (net (code "33") (name "Net-(U$15-PadOUT_A)") (class "Default")
      (node (ref "U$15") (pin "OUT_A") (pinfunction "OUT_A_OUT_A") (pintype "bidirectional"))
      (node (ref "U$16") (pin "N1G") (pinfunction "N1G_N1G") (pintype "bidirectional"))
      (node (ref "U$16") (pin "P1G") (pinfunction "P1G_P1G") (pintype "bidirectional"))
    )
    (net (code "34") (name "Net-(U$15-PadOUT_B)") (class "Default")
      (node (ref "U$15") (pin "OUT_B") (pinfunction "OUT_B_OUT_B") (pintype "bidirectional"))
      (node (ref "U$16") (pin "N2G") (pinfunction "N2G_N2G") (pintype "bidirectional"))
      (node (ref "U$16") (pin "P2G") (pinfunction "P2G_P2G") (pintype "bidirectional"))
    )
    (net (code "35") (name "Net-(U$17-PadOUT_A)") (class "Default")
      (node (ref "U$17") (pin "OUT_A") (pinfunction "OUT_A_OUT_A") (pintype "bidirectional"))
      (node (ref "U$18") (pin "N1G") (pinfunction "N1G_N1G") (pintype "bidirectional"))
      (node (ref "U$18") (pin "P1G") (pinfunction "P1G_P1G") (pintype "bidirectional"))
    )
    (net (code "36") (name "Net-(U$17-PadOUT_B)") (class "Default")
      (node (ref "U$17") (pin "OUT_B") (pinfunction "OUT_B_OUT_B") (pintype "bidirectional"))
      (node (ref "U$18") (pin "N2G") (pinfunction "N2G_N2G") (pintype "bidirectional"))
      (node (ref "U$18") (pin "P2G") (pinfunction "P2G_P2G") (pintype "bidirectional"))
    )
    (net (code "37") (name "OSC_IN") (class "Default")
      (node (ref "C1") (pin "1") (pinfunction "1_1") (pintype "passive"))
      (node (ref "U$1") (pin "PH0") (pinfunction "PH0_PH0") (pintype "bidirectional"))
      (node (ref "U$2") (pin "P$2") (pinfunction "IN2_P$2") (pintype "bidirectional"))
    )
    (net (code "38") (name "OSC_OUT") (class "Default")
      (node (ref "C2") (pin "1") (pinfunction "1_1") (pintype "passive"))
      (node (ref "U$1") (pin "PH1") (pinfunction "PH1_PH1") (pintype "bidirectional"))
      (node (ref "U$2") (pin "P$1") (pinfunction "IN1_P$1") (pintype "bidirectional"))
    )
    (net (code "39") (name "RENCA") (class "Default")
      (node (ref "RIGHTMOTOR") (pin "6") (pinfunction "6_6") (pintype "passive"))
      (node (ref "RM") (pin "3") (pinfunction "3_3") (pintype "bidirectional"))
    )
    (net (code "40") (name "RENCB") (class "Default")
      (node (ref "RIGHTMOTOR") (pin "5") (pinfunction "5_5") (pintype "passive"))
      (node (ref "RM") (pin "4") (pinfunction "4_4") (pintype "bidirectional"))
    )
    (net (code "41") (name "RESET") (class "Default")
      (node (ref "SWD") (pin "1") (pinfunction "1_1") (pintype "bidirectional"))
      (node (ref "U$1") (pin "NRST") (pinfunction "NRST_NRST") (pintype "bidirectional"))
    )
    (net (code "42") (name "RE_L") (class "Default")
      (node (ref "IRRL") (pin "1") (pinfunction "1_1") (pintype "passive"))
      (node (ref "RRE5") (pin "2") (pinfunction "2_2") (pintype "passive"))
      (node (ref "U$1") (pin "PA2") (pinfunction "PA2_PA2") (pintype "bidirectional"))
    )
    (net (code "43") (name "RE_LFA") (class "Default")
      (node (ref "IRRLF") (pin "2") (pinfunction "2_2") (pintype "passive"))
      (node (ref "RRE1") (pin "2") (pinfunction "2_2") (pintype "passive"))
      (node (ref "U$1") (pin "PC1") (pinfunction "PC1_PC1") (pintype "bidirectional"))
    )
    (net (code "44") (name "RE_LFB") (class "Default")
      (node (ref "IRRLF") (pin "1") (pinfunction "1_1") (pintype "passive"))
      (node (ref "RRE2") (pin "2") (pinfunction "2_2") (pintype "passive"))
      (node (ref "U$1") (pin "PC2") (pinfunction "PC2_PC2") (pintype "bidirectional"))
    )
    (net (code "45") (name "RE_R") (class "Default")
      (node (ref "IRRR") (pin "1") (pinfunction "1_1") (pintype "passive"))
      (node (ref "RRE6") (pin "2") (pinfunction "2_2") (pintype "passive"))
      (node (ref "U$1") (pin "PB0") (pinfunction "PB0_PB0") (pintype "bidirectional"))
    )
    (net (code "46") (name "RE_RFA") (class "Default")
      (node (ref "IRRRF") (pin "1") (pinfunction "1_1") (pintype "passive"))
      (node (ref "RRE3") (pin "2") (pinfunction "2_2") (pintype "passive"))
      (node (ref "U$1") (pin "PC4") (pinfunction "PC4_PC4") (pintype "bidirectional"))
    )
    (net (code "47") (name "RE_RFB") (class "Default")
      (node (ref "IRRRF") (pin "2") (pinfunction "2_2") (pintype "passive"))
      (node (ref "RRE4") (pin "2") (pinfunction "2_2") (pintype "passive"))
      (node (ref "U$1") (pin "PC5") (pinfunction "PC5_PC5") (pintype "bidirectional"))
    )
    (net (code "48") (name "RPWMA") (class "Default")
      (node (ref "RM") (pin "1") (pinfunction "1_1") (pintype "bidirectional"))
      (node (ref "R_RMC_1") (pin "2") (pinfunction "2_2") (pintype "passive"))
      (node (ref "U$17") (pin "IN_B") (pinfunction "IN_B_IN_B") (pintype "bidirectional"))
    )
    (net (code "49") (name "RPWMB") (class "Default")
      (node (ref "RM") (pin "2") (pinfunction "2_2") (pintype "bidirectional"))
      (node (ref "R_RMC_2") (pin "2") (pinfunction "2_2") (pintype "passive"))
      (node (ref "U$17") (pin "IN_A") (pinfunction "IN_A_IN_A") (pintype "bidirectional"))
    )
    (net (code "50") (name "SPI2_MISO") (class "Default")
      (node (ref "SPI2") (pin "3") (pinfunction "3_3") (pintype "bidirectional"))
      (node (ref "U$1") (pin "PB14") (pinfunction "PB14_PB14") (pintype "bidirectional"))
    )
    (net (code "51") (name "SPI2_MOSI") (class "Default")
      (node (ref "SPI2") (pin "4") (pinfunction "4_4") (pintype "bidirectional"))
      (node (ref "U$1") (pin "PB15") (pinfunction "PB15_PB15") (pintype "bidirectional"))
    )
    (net (code "52") (name "SPI2_NSS") (class "Default")
      (node (ref "SPI2") (pin "1") (pinfunction "1_1") (pintype "bidirectional"))
      (node (ref "U$1") (pin "PB12") (pinfunction "PB12_PB12") (pintype "bidirectional"))
    )
    (net (code "53") (name "SPI2_SCK") (class "Default")
      (node (ref "SPI2") (pin "2") (pinfunction "2_2") (pintype "bidirectional"))
      (node (ref "U$1") (pin "PB13") (pinfunction "PB13_PB13") (pintype "bidirectional"))
    )
    (net (code "54") (name "SWCLK") (class "Default")
      (node (ref "SWD") (pin "4") (pinfunction "4_4") (pintype "bidirectional"))
      (node (ref "U$1") (pin "PA14") (pinfunction "PA14_PA14") (pintype "bidirectional"))
    )
    (net (code "55") (name "SWDIO") (class "Default")
      (node (ref "SWD") (pin "2") (pinfunction "2_2") (pintype "bidirectional"))
      (node (ref "U$1") (pin "PA13") (pinfunction "PA13_PA13") (pintype "bidirectional"))
    )
    (net (code "56") (name "TAB1") (class "Default")
      (node (ref "REG2") (pin "4") (pinfunction "TAB_4") (pintype "power_in"))
    )
    (net (code "57") (name "VBAT") (class "Default")
      (node (ref "CLMC_1") (pin "2") (pinfunction "2_2") (pintype "passive"))
      (node (ref "CLMC_2") (pin "A") (pinfunction "+_A") (pintype "passive"))
      (node (ref "CPWR_1") (pin "1") (pinfunction "1_1") (pintype "passive"))
      (node (ref "CPWR_5") (pin "1") (pinfunction "1_1") (pintype "passive"))
      (node (ref "CRMC_1") (pin "2") (pinfunction "2_2") (pintype "passive"))
      (node (ref "CRMC_2") (pin "A") (pinfunction "+_A") (pintype "passive"))
      (node (ref "P1") (pin "1") (pinfunction "1_1") (pintype "passive"))
      (node (ref "REG1") (pin "1") (pinfunction "VIN_1") (pintype "input"))
      (node (ref "REG3") (pin "1") (pinfunction "VIN_1") (pintype "input"))
      (node (ref "R_VMTR_2") (pin "2") (pinfunction "2_2") (pintype "passive"))
      (node (ref "U$15") (pin "VDD") (pinfunction "VDD_VDD") (pintype "bidirectional"))
      (node (ref "U$16") (pin "P1S/P2S") (pinfunction "P1S/P2S_P1S/P2S") (pintype "bidirectional"))
      (node (ref "U$17") (pin "VDD") (pinfunction "VDD_VDD") (pintype "bidirectional"))
      (node (ref "U$18") (pin "P1S/P2S") (pinfunction "P1S/P2S_P1S/P2S") (pintype "bidirectional"))
    )
    (net (code "58") (name "VMTR") (class "Default")
      (node (ref "R_VMTR_1") (pin "2") (pinfunction "2_2") (pintype "passive"))
      (node (ref "R_VMTR_2") (pin "1") (pinfunction "1_1") (pintype "passive"))
      (node (ref "U$1") (pin "PB1") (pinfunction "PB1_PB1") (pintype "bidirectional"))
    )
    (net (code "59") (name "unconnected-(U$1-PA0_AKUP-PadPA0_WKUP)") (class "Default")
      (node (ref "U$1") (pin "PA0_WKUP") (pinfunction "PA0_AKUP_PA0_WKUP") (pintype "bidirectional"))
    )
    (net (code "60") (name "unconnected-(U$1-PadPA1)") (class "Default")
      (node (ref "U$1") (pin "PA1") (pinfunction "PA1_PA1") (pintype "bidirectional"))
    )
    (net (code "61") (name "unconnected-(U$1-PadPA3)") (class "Default")
      (node (ref "U$1") (pin "PA3") (pinfunction "PA3_PA3") (pintype "bidirectional"))
    )
    (net (code "62") (name "unconnected-(U$1-PadPA4)") (class "Default")
      (node (ref "U$1") (pin "PA4") (pinfunction "PA4_PA4") (pintype "bidirectional"))
    )
    (net (code "63") (name "unconnected-(U$1-PadPA5)") (class "Default")
      (node (ref "U$1") (pin "PA5") (pinfunction "PA5_PA5") (pintype "bidirectional"))
    )
    (net (code "64") (name "unconnected-(U$1-PadPA6)") (class "Default")
      (node (ref "U$1") (pin "PA6") (pinfunction "PA6_PA6") (pintype "bidirectional"))
    )
    (net (code "65") (name "unconnected-(U$1-PadPA7)") (class "Default")
      (node (ref "U$1") (pin "PA7") (pinfunction "PA7_PA7") (pintype "bidirectional"))
    )
    (net (code "66") (name "unconnected-(U$1-PadPA12)") (class "Default")
      (node (ref "U$1") (pin "PA12") (pinfunction "PA12_PA12") (pintype "bidirectional"))
    )
    (net (code "67") (name "unconnected-(U$1-PadPA15)") (class "Default")
      (node (ref "U$1") (pin "PA15") (pinfunction "PA15_PA15") (pintype "bidirectional"))
    )
    (net (code "68") (name "unconnected-(U$1-PadPB3)") (class "Default")
      (node (ref "U$1") (pin "PB3") (pinfunction "PB3_PB3") (pintype "bidirectional"))
    )
    (net (code "69") (name "unconnected-(U$1-PadPB4)") (class "Default")
      (node (ref "U$1") (pin "PB4") (pinfunction "PB4_PB4") (pintype "bidirectional"))
    )
    (net (code "70") (name "unconnected-(U$1-PadPB5)") (class "Default")
      (node (ref "U$1") (pin "PB5") (pinfunction "PB5_PB5") (pintype "bidirectional"))
    )
    (net (code "71") (name "unconnected-(U$1-PadPB6)") (class "Default")
      (node (ref "U$1") (pin "PB6") (pinfunction "PB6_PB6") (pintype "bidirectional"))
    )
    (net (code "72") (name "unconnected-(U$1-PadPB7)") (class "Default")
      (node (ref "U$1") (pin "PB7") (pinfunction "PB7_PB7") (pintype "bidirectional"))
    )
    (net (code "73") (name "unconnected-(U$1-PadPB8)") (class "Default")
      (node (ref "U$1") (pin "PB8") (pinfunction "PB8_PB8") (pintype "bidirectional"))
    )
    (net (code "74") (name "unconnected-(U$1-PadPB9)") (class "Default")
      (node (ref "U$1") (pin "PB9") (pinfunction "PB9_PB9") (pintype "bidirectional"))
    )
    (net (code "75") (name "unconnected-(U$1-PadPB10)") (class "Default")
      (node (ref "U$1") (pin "PB10") (pinfunction "PB10_PB10") (pintype "bidirectional"))
    )
    (net (code "76") (name "unconnected-(U$1-PadPB11)") (class "Default")
      (node (ref "U$1") (pin "PB11") (pinfunction "PB11_PB11") (pintype "bidirectional"))
    )
    (net (code "77") (name "unconnected-(U$1-PadPC0)") (class "Default")
      (node (ref "U$1") (pin "PC0") (pinfunction "PC0_PC0") (pintype "bidirectional"))
    )
    (net (code "78") (name "unconnected-(U$1-PadPC3)") (class "Default")
      (node (ref "U$1") (pin "PC3") (pinfunction "PC3_PC3") (pintype "bidirectional"))
    )
    (net (code "79") (name "unconnected-(U$1-PadPC6)") (class "Default")
      (node (ref "U$1") (pin "PC6") (pinfunction "PC6_PC6") (pintype "bidirectional"))
    )
    (net (code "80") (name "unconnected-(U$1-PadPC7)") (class "Default")
      (node (ref "U$1") (pin "PC7") (pinfunction "PC7_PC7") (pintype "bidirectional"))
    )
    (net (code "81") (name "unconnected-(U$1-PadPC8)") (class "Default")
      (node (ref "U$1") (pin "PC8") (pinfunction "PC8_PC8") (pintype "bidirectional"))
    )
    (net (code "82") (name "unconnected-(U$1-PadPC9)") (class "Default")
      (node (ref "U$1") (pin "PC9") (pinfunction "PC9_PC9") (pintype "bidirectional"))
    )
    (net (code "83") (name "unconnected-(U$1-PadPC10)") (class "Default")
      (node (ref "U$1") (pin "PC10") (pinfunction "PC10_PC10") (pintype "bidirectional"))
    )
    (net (code "84") (name "unconnected-(U$1-PadPC11)") (class "Default")
      (node (ref "U$1") (pin "PC11") (pinfunction "PC11_PC11") (pintype "bidirectional"))
    )
    (net (code "85") (name "unconnected-(U$1-PadPC12)") (class "Default")
      (node (ref "U$1") (pin "PC12") (pinfunction "PC12_PC12") (pintype "bidirectional"))
    )
    (net (code "86") (name "unconnected-(U$1-PadPC13)") (class "Default")
      (node (ref "U$1") (pin "PC13") (pinfunction "PC13_PC13") (pintype "bidirectional"))
    )
    (net (code "87") (name "unconnected-(U$1-PadPC14)") (class "Default")
      (node (ref "U$1") (pin "PC14") (pinfunction "PC14_PC14") (pintype "bidirectional"))
    )
    (net (code "88") (name "unconnected-(U$1-PadPC15)") (class "Default")
      (node (ref "U$1") (pin "PC15") (pinfunction "PC15_PC15") (pintype "bidirectional"))
    )
    (net (code "89") (name "unconnected-(U$1-PadPD2)") (class "Default")
      (node (ref "U$1") (pin "PD2") (pinfunction "PD2_PD2") (pintype "bidirectional"))
    )
    (net (code "90") (name "unconnected-(U$8-Pad1)") (class "Default")
      (node (ref "U$8") (pin "1") (pinfunction "1_1") (pintype "bidirectional"))
    )
    (net (code "91") (name "unconnected-(U$8-Pad2)") (class "Default")
      (node (ref "U$8") (pin "2") (pinfunction "2_2") (pintype "bidirectional"))
    )
    (net (code "92") (name "unconnected-(U$9-Pad1)") (class "Default")
      (node (ref "U$9") (pin "1") (pinfunction "1_1") (pintype "bidirectional"))
    )
    (net (code "93") (name "unconnected-(U$9-Pad2)") (class "Default")
      (node (ref "U$9") (pin "2") (pinfunction "2_2") (pintype "bidirectional"))
    )
    (net (code "94") (name "unconnected-(U$15-PadNC1)") (class "Default")
      (node (ref "U$15") (pin "NC1") (pinfunction "NC1_NC1") (pintype "bidirectional"))
    )
    (net (code "95") (name "unconnected-(U$15-PadNC2)") (class "Default")
      (node (ref "U$15") (pin "NC2") (pinfunction "NC2_NC2") (pintype "bidirectional"))
    )
    (net (code "96") (name "unconnected-(U$17-PadNC1)") (class "Default")
      (node (ref "U$17") (pin "NC1") (pinfunction "NC1_NC1") (pintype "bidirectional"))
    )
    (net (code "97") (name "unconnected-(U$17-PadNC2)") (class "Default")
      (node (ref "U$17") (pin "NC2") (pinfunction "NC2_NC2") (pintype "bidirectional"))
    )
  )
)
